# 1_RX_Ultrasonic.net
KiCad netlist of a schematic drawn in Altium Designer
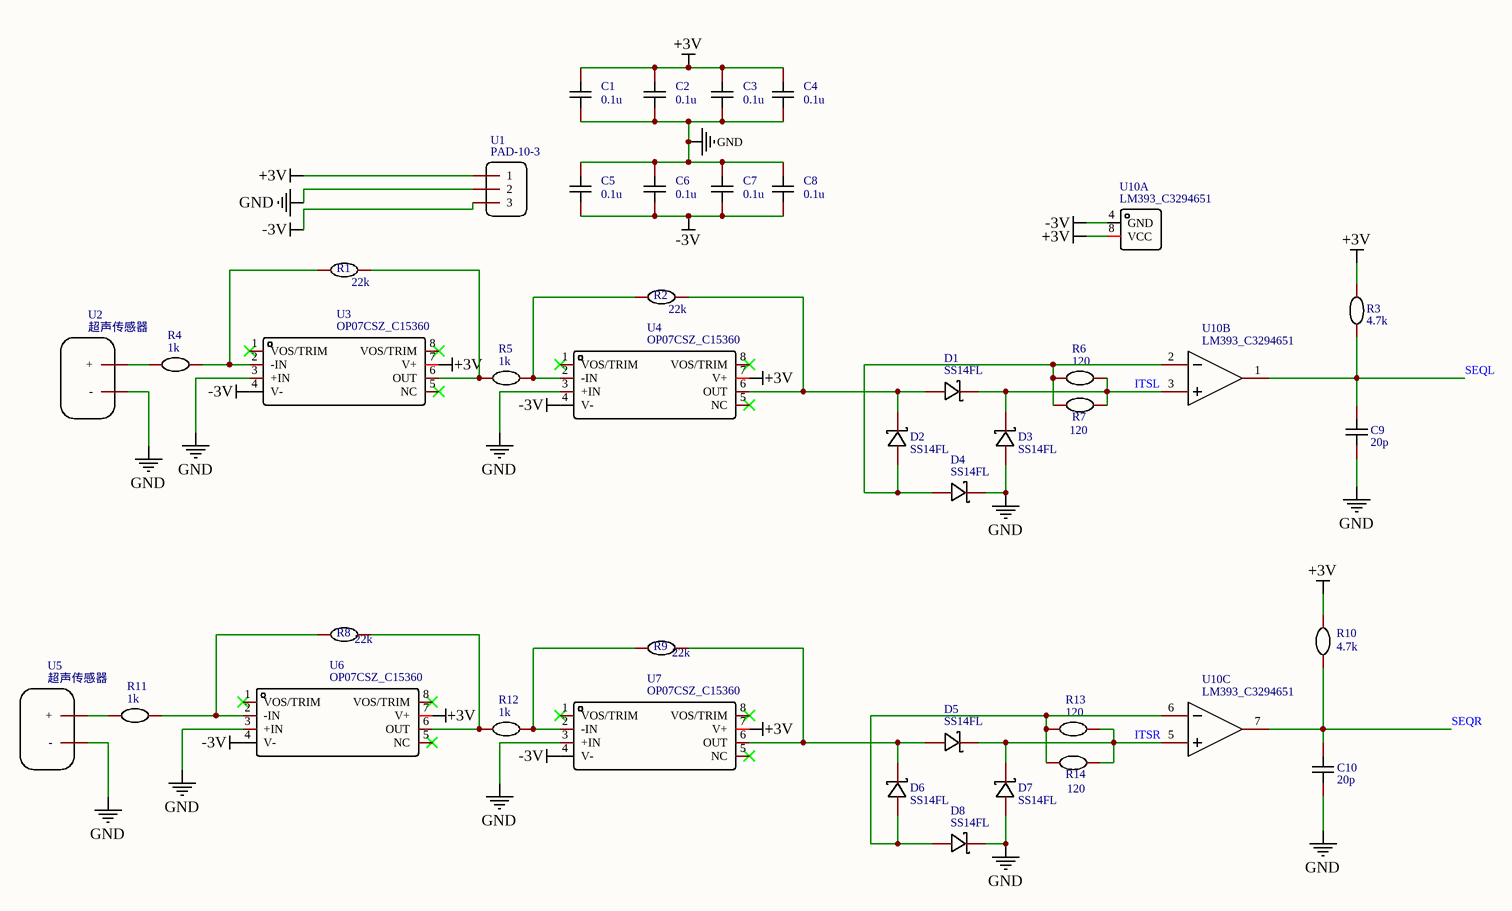
[diagram p0: 1_RX_Ultrasonic.schdoc]

(export (version "E")
  (design (tool "Eeschema 10.0.6"))
  (components
    (comp (ref "C1")
      (value "0.1u")
      (footprint "C0603")
      (fields (field (name "NAME") "0.1u"))
      (libsource (lib "altium-import") (part "root_3_0.1u_"))
    )
    (comp (ref "C2")
      (value "0.1u")
      (footprint "C0603")
      (fields (field (name "NAME") "0.1u"))
      (libsource (lib "altium-import") (part "root_3_0.1u_"))
    )
    (comp (ref "C3")
      (value "0.1u")
      (footprint "C0603")
      (fields (field (name "NAME") "0.1u"))
      (libsource (lib "altium-import") (part "root_3_0.1u_"))
    )
    (comp (ref "C4")
      (value "0.1u")
      (footprint "C0603")
      (fields (field (name "NAME") "0.1u"))
      (libsource (lib "altium-import") (part "root_3_0.1u_"))
    )
    (comp (ref "C5")
      (value "0.1u")
      (footprint "C0603")
      (fields (field (name "NAME") "0.1u"))
      (libsource (lib "altium-import") (part "root_3_0.1u_"))
    )
    (comp (ref "C6")
      (value "0.1u")
      (footprint "C0603")
      (fields (field (name "NAME") "0.1u"))
      (libsource (lib "altium-import") (part "root_3_0.1u_"))
    )
    (comp (ref "C7")
      (value "0.1u")
      (footprint "C0603")
      (fields (field (name "NAME") "0.1u"))
      (libsource (lib "altium-import") (part "root_3_0.1u_"))
    )
    (comp (ref "C8")
      (value "0.1u")
      (footprint "C0603")
      (fields (field (name "NAME") "0.1u"))
      (libsource (lib "altium-import") (part "root_3_0.1u_"))
    )
    (comp (ref "C9")
      (value "20p")
      (footprint "C0603")
      (fields (field (name "NAME") "20p"))
      (libsource (lib "altium-import") (part "root_1_20p_"))
    )
    (comp (ref "C10")
      (value "20p")
      (footprint "C0603")
      (fields (field (name "NAME") "20p"))
      (libsource (lib "altium-import") (part "root_1_20p_"))
    )
    (comp (ref "D1")
      (value "SS14FL")
      (footprint "SMA_L4.4-W2.8-LS5.4-RD")
      (fields (field (name "NAME") "SS14FL") (field (name "MANUFACTURER") "SK"))
      (libsource (lib "altium-import") (part "root_2_SS14FL_"))
    )
    (comp (ref "D2")
      (value "SS14FL")
      (footprint "SMA_L4.4-W2.8-LS5.4-RD")
      (fields (field (name "NAME") "SS14FL") (field (name "MANUFACTURER") "SK"))
      (libsource (lib "altium-import") (part "root_3_SS14FL_"))
    )
    (comp (ref "D3")
      (value "SS14FL")
      (footprint "SMA_L4.4-W2.8-LS5.4-RD")
      (fields (field (name "NAME") "SS14FL") (field (name "MANUFACTURER") "SK"))
      (libsource (lib "altium-import") (part "root_3_SS14FL_"))
    )
    (comp (ref "D4")
      (value "SS14FL")
      (footprint "SMA_L4.4-W2.8-LS5.4-RD")
      (fields (field (name "NAME") "SS14FL") (field (name "MANUFACTURER") "SK"))
      (libsource (lib "altium-import") (part "root_2_SS14FL_"))
    )
    (comp (ref "D5")
      (value "SS14FL")
      (footprint "SMA_L4.4-W2.8-LS5.4-RD")
      (fields (field (name "NAME") "SS14FL") (field (name "MANUFACTURER") "SK"))
      (libsource (lib "altium-import") (part "root_2_SS14FL_"))
    )
    (comp (ref "D6")
      (value "SS14FL")
      (footprint "SMA_L4.4-W2.8-LS5.4-RD")
      (fields (field (name "NAME") "SS14FL") (field (name "MANUFACTURER") "SK"))
      (libsource (lib "altium-import") (part "root_3_SS14FL_"))
    )
    (comp (ref "D7")
      (value "SS14FL")
      (footprint "SMA_L4.4-W2.8-LS5.4-RD")
      (fields (field (name "NAME") "SS14FL") (field (name "MANUFACTURER") "SK"))
      (libsource (lib "altium-import") (part "root_3_SS14FL_"))
    )
    (comp (ref "D8")
      (value "SS14FL")
      (footprint "SMA_L4.4-W2.8-LS5.4-RD")
      (fields (field (name "NAME") "SS14FL") (field (name "MANUFACTURER") "SK"))
      (libsource (lib "altium-import") (part "root_2_SS14FL_"))
    )
    (comp (ref "R1")
      (value "22k")
      (footprint "R0603")
      (fields (field (name "NAME") "22k"))
      (libsource (lib "altium-import") (part "root_0_22k_"))
    )
    (comp (ref "R2")
      (value "22k")
      (footprint "R0603")
      (fields (field (name "NAME") "22k"))
      (libsource (lib "altium-import") (part "root_0_22k_"))
    )
    (comp (ref "R3")
      (value "4.7k")
      (footprint "R0603")
      (fields (field (name "NAME") "4.7k"))
      (libsource (lib "altium-import") (part "root_3_4.7k_"))
    )
    (comp (ref "R4")
      (value "1k")
      (footprint "R0603")
      (fields (field (name "NAME") "1k"))
      (libsource (lib "altium-import") (part "root_0_1k_"))
    )
    (comp (ref "R5")
      (value "1k")
      (footprint "R0603")
      (fields (field (name "NAME") "1k"))
      (libsource (lib "altium-import") (part "root_0_1k_"))
    )
    (comp (ref "R6")
      (value "120")
      (footprint "R0603")
      (fields (field (name "NAME") "120"))
      (libsource (lib "altium-import") (part "root_2_120_"))
    )
    (comp (ref "R7")
      (value "120")
      (footprint "R0603")
      (fields (field (name "NAME") "120"))
      (libsource (lib "altium-import") (part "root_0_120_"))
    )
    (comp (ref "R8")
      (value "22k")
      (footprint "R0603")
      (fields (field (name "NAME") "22k"))
      (libsource (lib "altium-import") (part "root_0_22k_"))
    )
    (comp (ref "R9")
      (value "22k")
      (footprint "R0603")
      (fields (field (name "NAME") "22k"))
      (libsource (lib "altium-import") (part "root_0_22k_"))
    )
    (comp (ref "R10")
      (value "4.7k")
      (footprint "R0603")
      (fields (field (name "NAME") "4.7k"))
      (libsource (lib "altium-import") (part "root_3_4.7k_"))
    )
    (comp (ref "R11")
      (value "1k")
      (footprint "R0603")
      (fields (field (name "NAME") "1k"))
      (libsource (lib "altium-import") (part "root_0_1k_"))
    )
    (comp (ref "R12")
      (value "1k")
      (footprint "R0603")
      (fields (field (name "NAME") "1k"))
      (libsource (lib "altium-import") (part "root_0_1k_"))
    )
    (comp (ref "R13")
      (value "120")
      (footprint "R0603")
      (fields (field (name "NAME") "120"))
      (libsource (lib "altium-import") (part "root_0_120_"))
    )
    (comp (ref "R14")
      (value "120")
      (footprint "R0603")
      (fields (field (name "NAME") "120"))
      (libsource (lib "altium-import") (part "root_0_120_"))
    )
    (comp (ref "U1")
      (value "PAD-10-3")
      (footprint "PAD-10-3")
      (fields (field (name "NAME") "PAD-10-3"))
      (libsource (lib "altium-import") (part "root_0_PAD-10-3_"))
    )
    (comp (ref "U2")
      (value "超声传感器")
      (footprint "超声传感器")
      (fields (field (name "NAME") "超声传感器"))
      (libsource (lib "altium-import") (part "root_0_超声传感器_"))
    )
    (comp (ref "U3")
      (value "OP07CSZ")
      (footprint "SOIC-8_L4.9-W3.9-P1.27-LS6.0-BL")
      (fields (field (name "NAME") "OP07CSZ_C15360") (field (name "MANUFACTURER") "ADI(亚德诺)/LINEAR"))
      (libsource (lib "altium-import") (part "root_0_OP07CSZ_"))
    )
    (comp (ref "U4")
      (value "OP07CSZ")
      (footprint "SOIC-8_L4.9-W3.9-P1.27-LS6.0-BL")
      (fields (field (name "NAME") "OP07CSZ_C15360") (field (name "MANUFACTURER") "ADI(亚德诺)/LINEAR"))
      (libsource (lib "altium-import") (part "root_0_OP07CSZ_"))
    )
    (comp (ref "U5")
      (value "超声传感器")
      (footprint "超声传感器")
      (fields (field (name "NAME") "超声传感器"))
      (libsource (lib "altium-import") (part "root_0_超声传感器_"))
    )
    (comp (ref "U6")
      (value "OP07CSZ")
      (footprint "SOIC-8_L4.9-W3.9-P1.27-LS6.0-BL")
      (fields (field (name "NAME") "OP07CSZ_C15360") (field (name "MANUFACTURER") "ADI(亚德诺)/LINEAR"))
      (libsource (lib "altium-import") (part "root_0_OP07CSZ_"))
    )
    (comp (ref "U7")
      (value "OP07CSZ")
      (footprint "SOIC-8_L4.9-W3.9-P1.27-LS6.0-BL")
      (fields (field (name "NAME") "OP07CSZ_C15360") (field (name "MANUFACTURER") "ADI(亚德诺)/LINEAR"))
      (libsource (lib "altium-import") (part "root_0_OP07CSZ_"))
    )
    (comp (ref "U10")
      (value "LM393")
      (footprint "SOP-8_L5.0-W4.0-P1.27-LS6.0-BL")
      (fields (field (name "NAME") "LM393_C3294651") (field (name "MANUFACTURER") "DOWO(东沃)"))
      (libsource (lib "altium-import") (part "root_0_LM393_"))
    )
  )
  (nets
    (net (code "1") (name "+3V") (class "Default")
      (node (ref "C1") (pin "1") (pinfunction "1_1") (pintype "passive"))
      (node (ref "C2") (pin "1") (pinfunction "1_1") (pintype "passive"))
      (node (ref "C3") (pin "1") (pinfunction "1_1") (pintype "passive"))
      (node (ref "C4") (pin "1") (pinfunction "1_1") (pintype "passive"))
      (node (ref "R10") (pin "1") (pinfunction "1_1") (pintype "passive"))
      (node (ref "R3") (pin "1") (pinfunction "1_1") (pintype "passive"))
      (node (ref "U1") (pin "1") (pinfunction "1_1") (pintype "passive"))
      (node (ref "U10") (pin "8") (pinfunction "VCC_8") (pintype "passive"))
      (node (ref "U3") (pin "7") (pinfunction "V+_7") (pintype "passive"))
      (node (ref "U4") (pin "7") (pinfunction "V+_7") (pintype "passive"))
      (node (ref "U6") (pin "7") (pinfunction "V+_7") (pintype "passive"))
      (node (ref "U7") (pin "7") (pinfunction "V+_7") (pintype "passive"))
    )
    (net (code "2") (name "-3V") (class "Default")
      (node (ref "C5") (pin "2") (pinfunction "2_2") (pintype "passive"))
      (node (ref "C6") (pin "2") (pinfunction "2_2") (pintype "passive"))
      (node (ref "C7") (pin "2") (pinfunction "2_2") (pintype "passive"))
      (node (ref "C8") (pin "2") (pinfunction "2_2") (pintype "passive"))
      (node (ref "U1") (pin "3") (pinfunction "3_3") (pintype "passive"))
      (node (ref "U10") (pin "4") (pinfunction "GND_4") (pintype "passive"))
      (node (ref "U3") (pin "4") (pinfunction "V-_4") (pintype "passive"))
      (node (ref "U4") (pin "4") (pinfunction "V-_4") (pintype "passive"))
      (node (ref "U6") (pin "4") (pinfunction "V-_4") (pintype "passive"))
      (node (ref "U7") (pin "4") (pinfunction "V-_4") (pintype "passive"))
    )
    (net (code "3") (name "/ITSL") (class "Default")
      (node (ref "D1") (pin "1") (pinfunction "C_1") (pintype "passive"))
      (node (ref "D3") (pin "1") (pinfunction "C_1") (pintype "passive"))
      (node (ref "R6") (pin "1") (pinfunction "1_1") (pintype "passive"))
      (node (ref "R7") (pin "2") (pinfunction "2_2") (pintype "passive"))
      (node (ref "U10") (pin "3") (pinfunction "1IN+_3") (pintype "passive"))
    )
    (net (code "4") (name "/ITSR") (class "Default")
      (node (ref "D5") (pin "1") (pinfunction "C_1") (pintype "passive"))
      (node (ref "D7") (pin "1") (pinfunction "C_1") (pintype "passive"))
      (node (ref "R13") (pin "2") (pinfunction "2_2") (pintype "passive"))
      (node (ref "R14") (pin "2") (pinfunction "2_2") (pintype "passive"))
      (node (ref "U10") (pin "5") (pinfunction "2IN+_5") (pintype "passive"))
    )
    (net (code "5") (name "/SEQL") (class "Default")
      (node (ref "C9") (pin "2") (pinfunction "2_2") (pintype "passive"))
      (node (ref "R3") (pin "2") (pinfunction "2_2") (pintype "passive"))
      (node (ref "U10") (pin "1") (pinfunction "1OUT_1") (pintype "passive"))
    )
    (net (code "6") (name "/SEQR") (class "Default")
      (node (ref "C10") (pin "2") (pinfunction "2_2") (pintype "passive"))
      (node (ref "R10") (pin "2") (pinfunction "2_2") (pintype "passive"))
      (node (ref "U10") (pin "7") (pinfunction "2OUT_7") (pintype "passive"))
    )
    (net (code "7") (name "GND") (class "Default")
      (node (ref "C1") (pin "2") (pinfunction "2_2") (pintype "passive"))
      (node (ref "C10") (pin "1") (pinfunction "1_1") (pintype "passive"))
      (node (ref "C2") (pin "2") (pinfunction "2_2") (pintype "passive"))
      (node (ref "C3") (pin "2") (pinfunction "2_2") (pintype "passive"))
      (node (ref "C4") (pin "2") (pinfunction "2_2") (pintype "passive"))
      (node (ref "C5") (pin "1") (pinfunction "1_1") (pintype "passive"))
      (node (ref "C6") (pin "1") (pinfunction "1_1") (pintype "passive"))
      (node (ref "C7") (pin "1") (pinfunction "1_1") (pintype "passive"))
      (node (ref "C8") (pin "1") (pinfunction "1_1") (pintype "passive"))
      (node (ref "C9") (pin "1") (pinfunction "1_1") (pintype "passive"))
      (node (ref "D3") (pin "2") (pinfunction "A_2") (pintype "passive"))
      (node (ref "D4") (pin "1") (pinfunction "C_1") (pintype "passive"))
      (node (ref "D7") (pin "2") (pinfunction "A_2") (pintype "passive"))
      (node (ref "D8") (pin "1") (pinfunction "C_1") (pintype "passive"))
      (node (ref "U1") (pin "2") (pinfunction "2_2") (pintype "passive"))
      (node (ref "U2") (pin "2") (pinfunction "-_2") (pintype "passive"))
      (node (ref "U3") (pin "3") (pinfunction "+IN_3") (pintype "passive"))
      (node (ref "U4") (pin "3") (pinfunction "+IN_3") (pintype "passive"))
      (node (ref "U5") (pin "2") (pinfunction "-_2") (pintype "passive"))
      (node (ref "U6") (pin "3") (pinfunction "+IN_3") (pintype "passive"))
      (node (ref "U7") (pin "3") (pinfunction "+IN_3") (pintype "passive"))
    )
    (net (code "8") (name "Net-(D1-A)") (class "Default")
      (node (ref "D1") (pin "2") (pinfunction "A_2") (pintype "passive"))
      (node (ref "D2") (pin "1") (pinfunction "C_1") (pintype "passive"))
      (node (ref "R2") (pin "2") (pinfunction "2_2") (pintype "passive"))
      (node (ref "U4") (pin "6") (pinfunction "OUT_6") (pintype "passive"))
    )
    (net (code "9") (name "Net-(D2-A)") (class "Default")
      (node (ref "D2") (pin "2") (pinfunction "A_2") (pintype "passive"))
      (node (ref "D4") (pin "2") (pinfunction "A_2") (pintype "passive"))
      (node (ref "R6") (pin "2") (pinfunction "2_2") (pintype "passive"))
      (node (ref "R7") (pin "1") (pinfunction "1_1") (pintype "passive"))
      (node (ref "U10") (pin "2") (pinfunction "1IN-_2") (pintype "passive"))
    )
    (net (code "10") (name "Net-(D5-A)") (class "Default")
      (node (ref "D5") (pin "2") (pinfunction "A_2") (pintype "passive"))
      (node (ref "D6") (pin "1") (pinfunction "C_1") (pintype "passive"))
      (node (ref "R9") (pin "2") (pinfunction "2_2") (pintype "passive"))
      (node (ref "U7") (pin "6") (pinfunction "OUT_6") (pintype "passive"))
    )
    (net (code "11") (name "Net-(D6-A)") (class "Default")
      (node (ref "D6") (pin "2") (pinfunction "A_2") (pintype "passive"))
      (node (ref "D8") (pin "2") (pinfunction "A_2") (pintype "passive"))
      (node (ref "R13") (pin "1") (pinfunction "1_1") (pintype "passive"))
      (node (ref "R14") (pin "1") (pinfunction "1_1") (pintype "passive"))
      (node (ref "U10") (pin "6") (pinfunction "2IN-_6") (pintype "passive"))
    )
    (net (code "12") (name "Net-(U2-+)") (class "Default")
      (node (ref "R4") (pin "1") (pinfunction "1_1") (pintype "passive"))
      (node (ref "U2") (pin "1") (pinfunction "+_1") (pintype "passive"))
    )
    (net (code "13") (name "Net-(U3--IN)") (class "Default")
      (node (ref "R1") (pin "1") (pinfunction "1_1") (pintype "passive"))
      (node (ref "R4") (pin "2") (pinfunction "2_2") (pintype "passive"))
      (node (ref "U3") (pin "2") (pinfunction "-IN_2") (pintype "passive"))
    )
    (net (code "14") (name "Net-(U3-OUT)") (class "Default")
      (node (ref "R1") (pin "2") (pinfunction "2_2") (pintype "passive"))
      (node (ref "R5") (pin "1") (pinfunction "1_1") (pintype "passive"))
      (node (ref "U3") (pin "6") (pinfunction "OUT_6") (pintype "passive"))
    )
    (net (code "15") (name "Net-(U4--IN)") (class "Default")
      (node (ref "R2") (pin "1") (pinfunction "1_1") (pintype "passive"))
      (node (ref "R5") (pin "2") (pinfunction "2_2") (pintype "passive"))
      (node (ref "U4") (pin "2") (pinfunction "-IN_2") (pintype "passive"))
    )
    (net (code "16") (name "Net-(U5-+)") (class "Default")
      (node (ref "R11") (pin "1") (pinfunction "1_1") (pintype "passive"))
      (node (ref "U5") (pin "1") (pinfunction "+_1") (pintype "passive"))
    )
    (net (code "17") (name "Net-(U6--IN)") (class "Default")
      (node (ref "R11") (pin "2") (pinfunction "2_2") (pintype "passive"))
      (node (ref "R8") (pin "1") (pinfunction "1_1") (pintype "passive"))
      (node (ref "U6") (pin "2") (pinfunction "-IN_2") (pintype "passive"))
    )
    (net (code "18") (name "Net-(U6-OUT)") (class "Default")
      (node (ref "R12") (pin "1") (pinfunction "1_1") (pintype "passive"))
      (node (ref "R8") (pin "2") (pinfunction "2_2") (pintype "passive"))
      (node (ref "U6") (pin "6") (pinfunction "OUT_6") (pintype "passive"))
    )
    (net (code "19") (name "Net-(U7--IN)") (class "Default")
      (node (ref "R12") (pin "2") (pinfunction "2_2") (pintype "passive"))
      (node (ref "R9") (pin "1") (pinfunction "1_1") (pintype "passive"))
      (node (ref "U7") (pin "2") (pinfunction "-IN_2") (pintype "passive"))
    )
    (net (code "20") (name "unconnected-(U3-NC-Pad5)") (class "Default")
      (node (ref "U3") (pin "5") (pinfunction "NC_5") (pintype "passive+no_connect"))
    )
    (net (code "21") (name "unconnected-(U3-VOS{slash}TRIM-Pad1)") (class "Default")
      (node (ref "U3") (pin "1") (pinfunction "VOS/TRIM_1") (pintype "passive+no_connect"))
    )
    (net (code "22") (name "unconnected-(U3-VOS{slash}TRIM-Pad8)") (class "Default")
      (node (ref "U3") (pin "8") (pinfunction "VOS/TRIM_8") (pintype "passive+no_connect"))
    )
    (net (code "23") (name "unconnected-(U4-NC-Pad5)") (class "Default")
      (node (ref "U4") (pin "5") (pinfunction "NC_5") (pintype "passive+no_connect"))
    )
    (net (code "24") (name "unconnected-(U4-VOS{slash}TRIM-Pad1)") (class "Default")
      (node (ref "U4") (pin "1") (pinfunction "VOS/TRIM_1") (pintype "passive+no_connect"))
    )
    (net (code "25") (name "unconnected-(U4-VOS{slash}TRIM-Pad8)") (class "Default")
      (node (ref "U4") (pin "8") (pinfunction "VOS/TRIM_8") (pintype "passive+no_connect"))
    )
    (net (code "26") (name "unconnected-(U6-NC-Pad5)") (class "Default")
      (node (ref "U6") (pin "5") (pinfunction "NC_5") (pintype "passive+no_connect"))
    )
    (net (code "27") (name "unconnected-(U6-VOS{slash}TRIM-Pad1)") (class "Default")
      (node (ref "U6") (pin "1") (pinfunction "VOS/TRIM_1") (pintype "passive+no_connect"))
    )
    (net (code "28") (name "unconnected-(U6-VOS{slash}TRIM-Pad8)") (class "Default")
      (node (ref "U6") (pin "8") (pinfunction "VOS/TRIM_8") (pintype "passive+no_connect"))
    )
    (net (code "29") (name "unconnected-(U7-NC-Pad5)") (class "Default")
      (node (ref "U7") (pin "5") (pinfunction "NC_5") (pintype "passive+no_connect"))
    )
    (net (code "30") (name "unconnected-(U7-VOS{slash}TRIM-Pad1)") (class "Default")
      (node (ref "U7") (pin "1") (pinfunction "VOS/TRIM_1") (pintype "passive+no_connect"))
    )
    (net (code "31") (name "unconnected-(U7-VOS{slash}TRIM-Pad8)") (class "Default")
      (node (ref "U7") (pin "8") (pinfunction "VOS/TRIM_8") (pintype "passive+no_connect"))
    )
  )
)
